# OBC_My_INTERFACE.net
KiCad netlist of a schematic drawn in Altium Designer
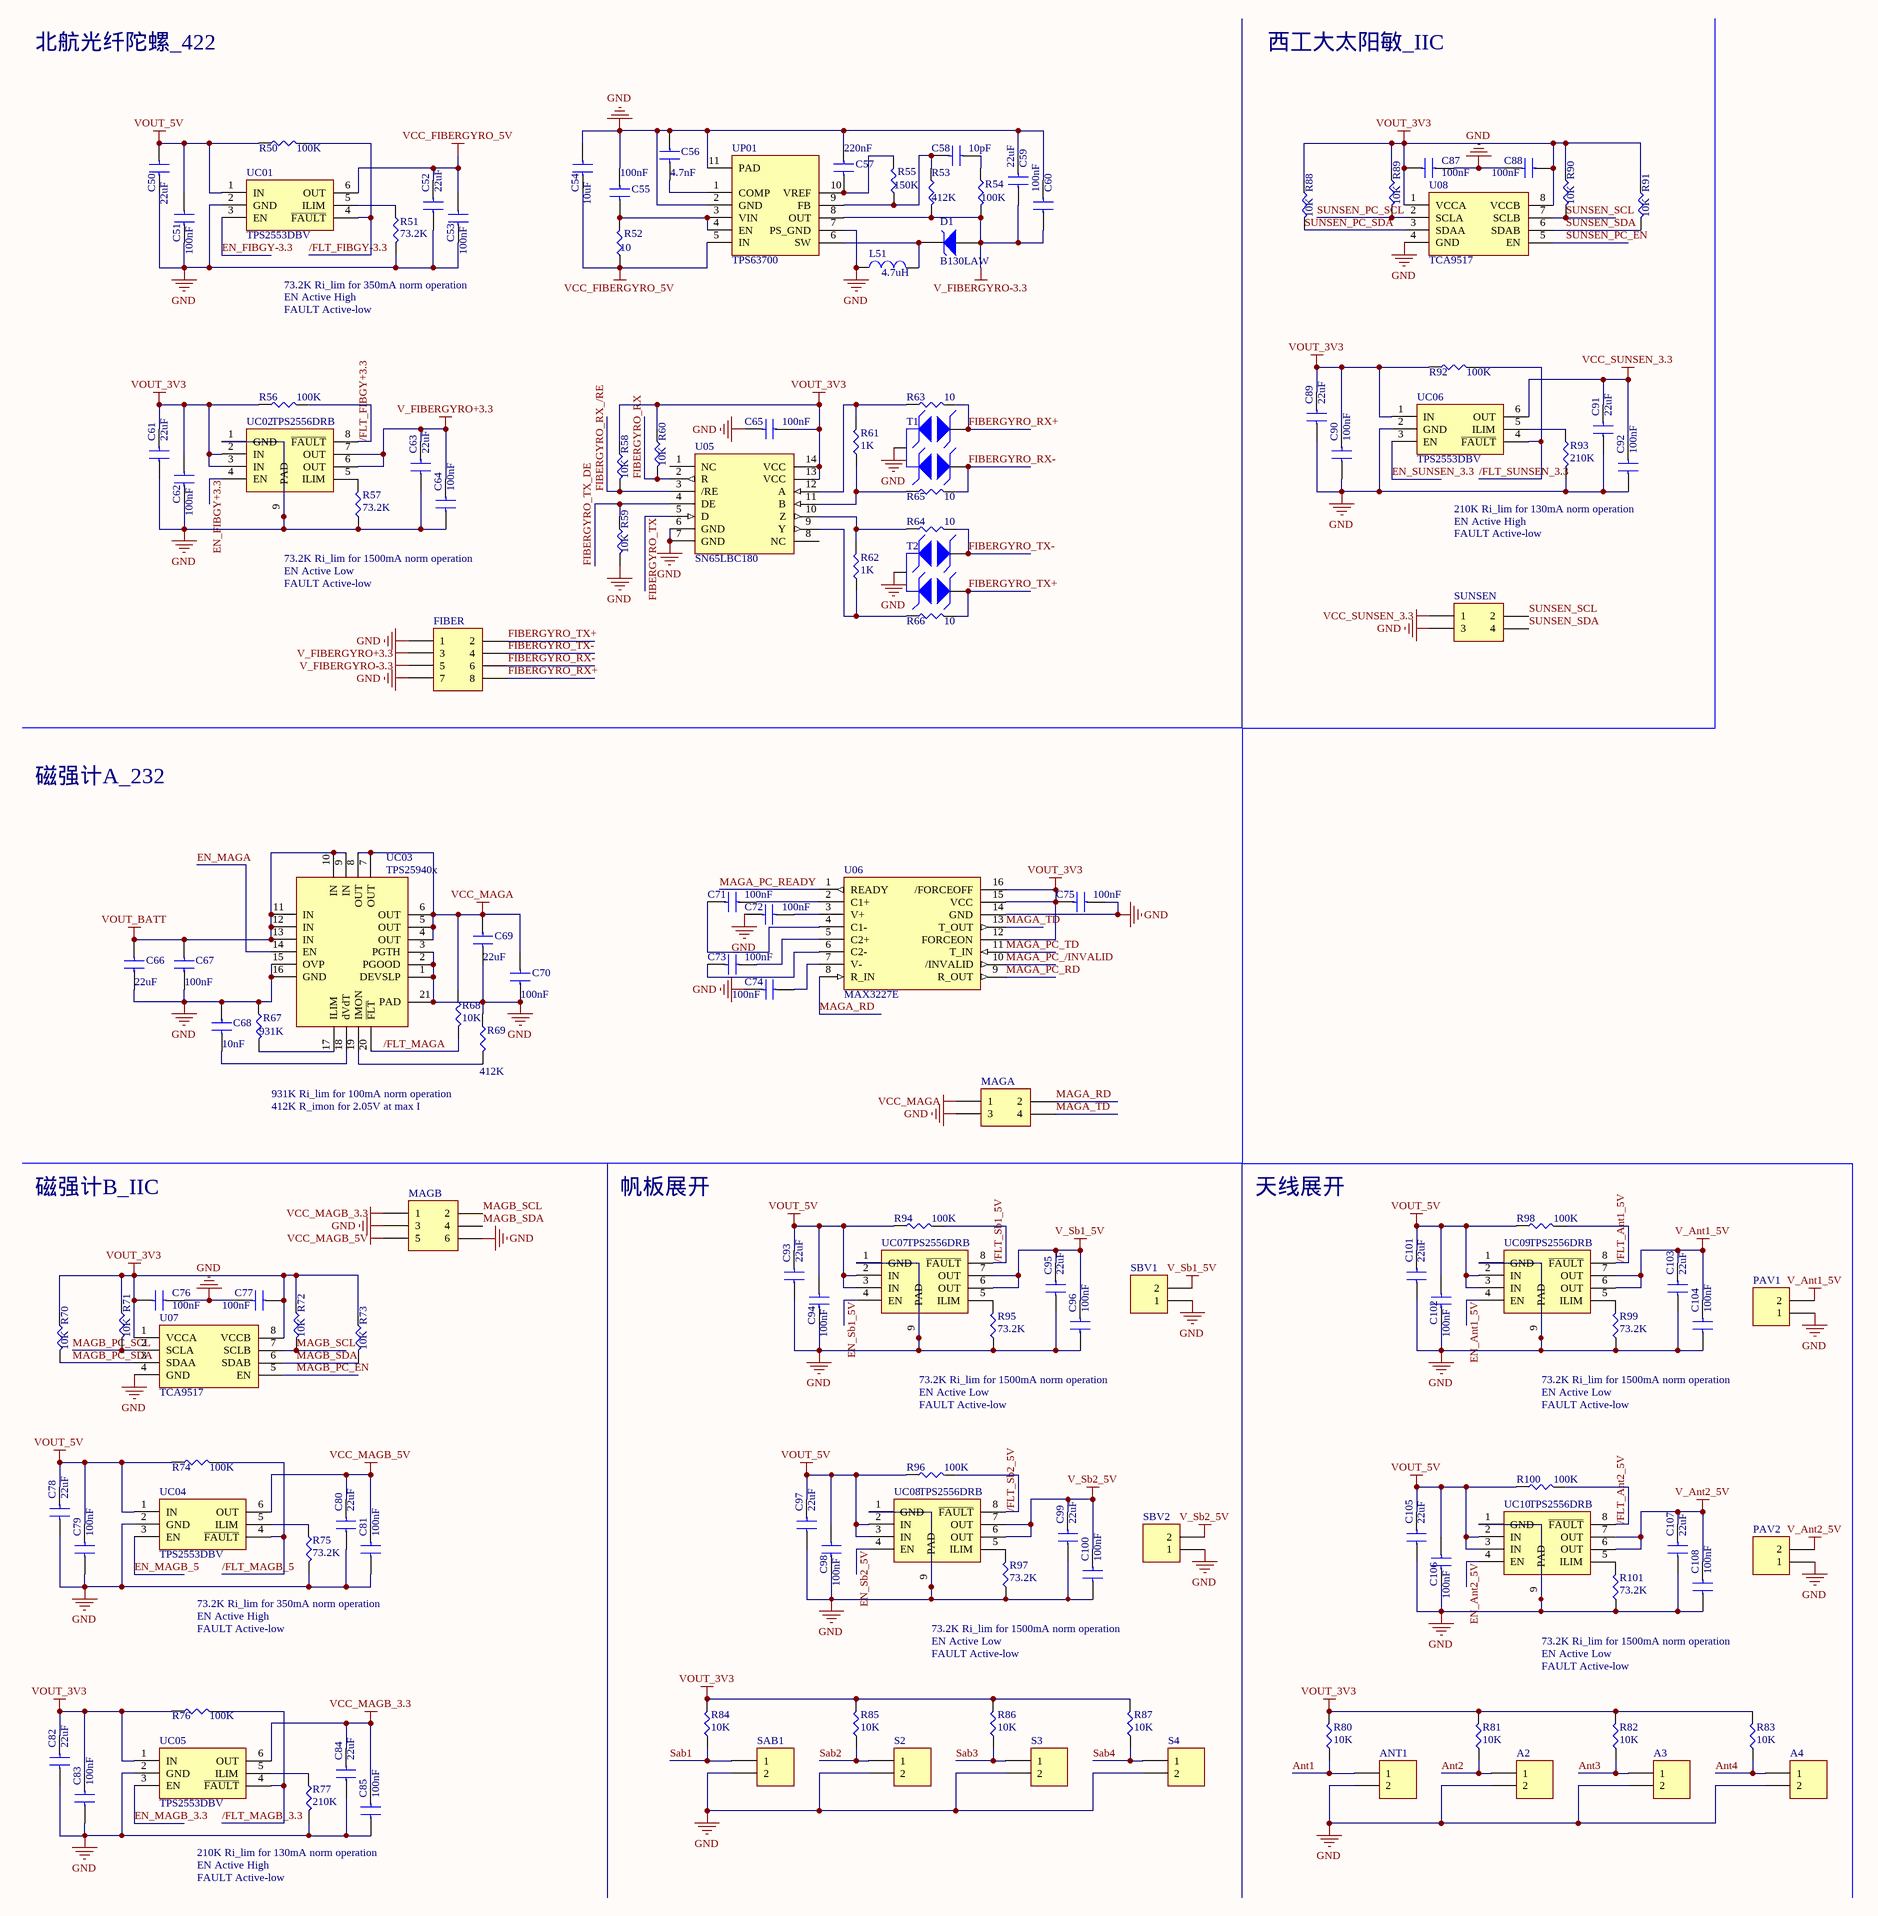
[diagram p0: OBC_My_INTERFACE.SchDoc]

(export (version "E")
  (design (tool "Eeschema 10.0.6"))
  (components
    (comp (ref "A2")
      (value "Header 2")
      (footprint "HDR1X2")
      (description "Header, 2-Pin")
      (fields (field (name "PUBLISHER") "Altium Limited"))
      (libsource (lib "Miscellaneous Connectors") (part "Header 2"))
    )
    (comp (ref "A3")
      (value "Header 2")
      (footprint "HDR1X2")
      (description "Header, 2-Pin")
      (fields (field (name "PUBLISHER") "Altium Limited"))
      (libsource (lib "Miscellaneous Connectors") (part "Header 2"))
    )
    (comp (ref "A4")
      (value "Header 2")
      (footprint "HDR1X2")
      (description "Header, 2-Pin")
      (fields (field (name "PUBLISHER") "Altium Limited"))
      (libsource (lib "Miscellaneous Connectors") (part "Header 2"))
    )
    (comp (ref "ANT1")
      (value "Header 2")
      (footprint "HDR1X2")
      (description "Header, 2-Pin")
      (fields (field (name "PUBLISHER") "Altium Limited"))
      (libsource (lib "Miscellaneous Connectors") (part "Header 2"))
    )
    (comp (ref "C50")
      (value "22uF")
      (footprint "1210(3225)-C-IPC")
      (description "Nonpolarized Capacitor (Surface Mount)")
      (libsource (lib "General Components") (part "Cap_1"))
    )
    (comp (ref "C51")
      (value "100nF")
      (footprint "0805(2012)-C-IPC")
      (description "Nonpolarized Capacitor (Surface Mount)")
      (libsource (lib "General Components") (part "Cap_1"))
    )
    (comp (ref "C52")
      (value "22uF")
      (footprint "1210(3225)-C-IPC")
      (description "Nonpolarized Capacitor (Surface Mount)")
      (libsource (lib "General Components") (part "Cap_1"))
    )
    (comp (ref "C53")
      (value "100nF")
      (footprint "0805(2012)-C-IPC")
      (description "Nonpolarized Capacitor (Surface Mount)")
      (libsource (lib "General Components") (part "Cap_1"))
    )
    (comp (ref "C54")
      (value "10uF")
      (footprint "0805(2012)-C-IPC")
      (description "Nonpolarized Capacitor (Surface Mount)")
      (libsource (lib "General Components") (part "Cap_1"))
    )
    (comp (ref "C55")
      (value "100nF")
      (footprint "0603(1608)-C-IPC")
      (description "Nonpolarized Capacitor (Surface Mount)")
      (libsource (lib "General Components") (part "Cap_1"))
    )
    (comp (ref "C56")
      (value "4.7nF")
      (footprint "0603(1608)-C-IPC")
      (description "Nonpolarized Capacitor (Surface Mount)")
      (libsource (lib "General Components") (part "Cap_1"))
    )
    (comp (ref "C57")
      (value "220nF")
      (footprint "0603(1608)-C-IPC")
      (description "Nonpolarized Capacitor (Surface Mount)")
      (libsource (lib "General Components") (part "Cap_1"))
    )
    (comp (ref "C58")
      (value "10pF")
      (footprint "0603(1608)-C-IPC")
      (description "Nonpolarized Capacitor (Surface Mount)")
      (libsource (lib "General Components") (part "Cap_1"))
    )
    (comp (ref "C59")
      (value "22uF")
      (footprint "1210(3225)-C-IPC")
      (description "Nonpolarized Capacitor (Surface Mount)")
      (libsource (lib "General Components") (part "Cap_1"))
    )
    (comp (ref "C60")
      (value "100nF")
      (footprint "0805(2012)-C-IPC")
      (description "Nonpolarized Capacitor (Surface Mount)")
      (libsource (lib "General Components") (part "Cap_1"))
    )
    (comp (ref "C61")
      (value "22uF")
      (footprint "1210(3225)-C-IPC")
      (description "Nonpolarized Capacitor (Surface Mount)")
      (libsource (lib "General Components") (part "Cap_1"))
    )
    (comp (ref "C62")
      (value "100nF")
      (footprint "0805(2012)-C-IPC")
      (description "Nonpolarized Capacitor (Surface Mount)")
      (libsource (lib "General Components") (part "Cap_1"))
    )
    (comp (ref "C63")
      (value "22uF")
      (footprint "1210(3225)-C-IPC")
      (description "Nonpolarized Capacitor (Surface Mount)")
      (libsource (lib "General Components") (part "Cap_1"))
    )
    (comp (ref "C64")
      (value "100nF")
      (footprint "0805(2012)-C-IPC")
      (description "Nonpolarized Capacitor (Surface Mount)")
      (libsource (lib "General Components") (part "Cap_1"))
    )
    (comp (ref "C65")
      (value "100nF")
      (footprint "0603(1608)-C-IPC")
      (description "Nonpolarized Capacitor (Surface Mount)")
      (libsource (lib "General Components") (part "Cap_1"))
    )
    (comp (ref "C66")
      (value "22uF")
      (footprint "1210(3225)-C-IPC")
      (description "Nonpolarized Capacitor (Surface Mount)")
      (libsource (lib "General Components") (part "Cap_1"))
    )
    (comp (ref "C67")
      (value "100nF")
      (footprint "0805(2012)-C-IPC")
      (description "Nonpolarized Capacitor (Surface Mount)")
      (libsource (lib "General Components") (part "Cap_1"))
    )
    (comp (ref "C68")
      (value "10nF")
      (footprint "0603(1608)-C-IPC")
      (description "Nonpolarized Capacitor (Surface Mount)")
      (libsource (lib "General Components") (part "Cap_1"))
    )
    (comp (ref "C69")
      (value "22uF")
      (footprint "1210(3225)-C-IPC")
      (description "Nonpolarized Capacitor (Surface Mount)")
      (libsource (lib "General Components") (part "Cap_1"))
    )
    (comp (ref "C70")
      (value "100nF")
      (footprint "0805(2012)-C-IPC")
      (description "Nonpolarized Capacitor (Surface Mount)")
      (libsource (lib "General Components") (part "Cap_1"))
    )
    (comp (ref "C71")
      (value "100nF")
      (footprint "0603(1608)-C-IPC")
      (description "Nonpolarized Capacitor (Surface Mount)")
      (libsource (lib "General Components") (part "Cap_1"))
    )
    (comp (ref "C72")
      (value "100nF")
      (footprint "0603(1608)-C-IPC")
      (description "Nonpolarized Capacitor (Surface Mount)")
      (libsource (lib "General Components") (part "Cap_1"))
    )
    (comp (ref "C73")
      (value "100nF")
      (footprint "0603(1608)-C-IPC")
      (description "Nonpolarized Capacitor (Surface Mount)")
      (libsource (lib "General Components") (part "Cap_1"))
    )
    (comp (ref "C74")
      (value "100nF")
      (footprint "0603(1608)-C-IPC")
      (description "Nonpolarized Capacitor (Surface Mount)")
      (libsource (lib "General Components") (part "Cap_1"))
    )
    (comp (ref "C75")
      (value "100nF")
      (footprint "0603(1608)-C-IPC")
      (description "Nonpolarized Capacitor (Surface Mount)")
      (libsource (lib "General Components") (part "Cap_1"))
    )
    (comp (ref "C76")
      (value "100nF")
      (footprint "0603(1608)-C-IPC")
      (description "Nonpolarized Capacitor (Surface Mount)")
      (libsource (lib "General Components") (part "Cap_1"))
    )
    (comp (ref "C77")
      (value "100nF")
      (footprint "0603(1608)-C-IPC")
      (description "Nonpolarized Capacitor (Surface Mount)")
      (libsource (lib "General Components") (part "Cap_1"))
    )
    (comp (ref "C78")
      (value "22uF")
      (footprint "1210(3225)-C-IPC")
      (description "Nonpolarized Capacitor (Surface Mount)")
      (libsource (lib "General Components") (part "Cap_1"))
    )
    (comp (ref "C79")
      (value "100nF")
      (footprint "0805(2012)-C-IPC")
      (description "Nonpolarized Capacitor (Surface Mount)")
      (libsource (lib "General Components") (part "Cap_1"))
    )
    (comp (ref "C80")
      (value "22uF")
      (footprint "1210(3225)-C-IPC")
      (description "Nonpolarized Capacitor (Surface Mount)")
      (libsource (lib "General Components") (part "Cap_1"))
    )
    (comp (ref "C81")
      (value "100nF")
      (footprint "0805(2012)-C-IPC")
      (description "Nonpolarized Capacitor (Surface Mount)")
      (libsource (lib "General Components") (part "Cap_1"))
    )
    (comp (ref "C82")
      (value "22uF")
      (footprint "1210(3225)-C-IPC")
      (description "Nonpolarized Capacitor (Surface Mount)")
      (libsource (lib "General Components") (part "Cap_1"))
    )
    (comp (ref "C83")
      (value "100nF")
      (footprint "0805(2012)-C-IPC")
      (description "Nonpolarized Capacitor (Surface Mount)")
      (libsource (lib "General Components") (part "Cap_1"))
    )
    (comp (ref "C84")
      (value "22uF")
      (footprint "1210(3225)-C-IPC")
      (description "Nonpolarized Capacitor (Surface Mount)")
      (libsource (lib "General Components") (part "Cap_1"))
    )
    (comp (ref "C85")
      (value "100nF")
      (footprint "0805(2012)-C-IPC")
      (description "Nonpolarized Capacitor (Surface Mount)")
      (libsource (lib "General Components") (part "Cap_1"))
    )
    (comp (ref "C87")
      (value "100nF")
      (footprint "0603(1608)-C-IPC")
      (description "Nonpolarized Capacitor (Surface Mount)")
      (libsource (lib "General Components") (part "Cap_1"))
    )
    (comp (ref "C88")
      (value "100nF")
      (footprint "0603(1608)-C-IPC")
      (description "Nonpolarized Capacitor (Surface Mount)")
      (libsource (lib "General Components") (part "Cap_1"))
    )
    (comp (ref "C89")
      (value "22uF")
      (footprint "1210(3225)-C-IPC")
      (description "Nonpolarized Capacitor (Surface Mount)")
      (libsource (lib "General Components") (part "Cap_1"))
    )
    (comp (ref "C90")
      (value "100nF")
      (footprint "0805(2012)-C-IPC")
      (description "Nonpolarized Capacitor (Surface Mount)")
      (libsource (lib "General Components") (part "Cap_1"))
    )
    (comp (ref "C91")
      (value "22uF")
      (footprint "1210(3225)-C-IPC")
      (description "Nonpolarized Capacitor (Surface Mount)")
      (libsource (lib "General Components") (part "Cap_1"))
    )
    (comp (ref "C92")
      (value "100nF")
      (footprint "0805(2012)-C-IPC")
      (description "Nonpolarized Capacitor (Surface Mount)")
      (libsource (lib "General Components") (part "Cap_1"))
    )
    (comp (ref "C93")
      (value "22uF")
      (footprint "1210(3225)-C-IPC")
      (description "Nonpolarized Capacitor (Surface Mount)")
      (libsource (lib "General Components") (part "Cap_1"))
    )
    (comp (ref "C94")
      (value "100nF")
      (footprint "0805(2012)-C-IPC")
      (description "Nonpolarized Capacitor (Surface Mount)")
      (libsource (lib "General Components") (part "Cap_1"))
    )
    (comp (ref "C95")
      (value "22uF")
      (footprint "1210(3225)-C-IPC")
      (description "Nonpolarized Capacitor (Surface Mount)")
      (libsource (lib "General Components") (part "Cap_1"))
    )
    (comp (ref "C96")
      (value "100nF")
      (footprint "0805(2012)-C-IPC")
      (description "Nonpolarized Capacitor (Surface Mount)")
      (libsource (lib "General Components") (part "Cap_1"))
    )
    (comp (ref "C97")
      (value "22uF")
      (footprint "1210(3225)-C-IPC")
      (description "Nonpolarized Capacitor (Surface Mount)")
      (libsource (lib "General Components") (part "Cap_1"))
    )
    (comp (ref "C98")
      (value "100nF")
      (footprint "0805(2012)-C-IPC")
      (description "Nonpolarized Capacitor (Surface Mount)")
      (libsource (lib "General Components") (part "Cap_1"))
    )
    (comp (ref "C99")
      (value "22uF")
      (footprint "1210(3225)-C-IPC")
      (description "Nonpolarized Capacitor (Surface Mount)")
      (libsource (lib "General Components") (part "Cap_1"))
    )
    (comp (ref "C100")
      (value "100nF")
      (footprint "0805(2012)-C-IPC")
      (description "Nonpolarized Capacitor (Surface Mount)")
      (libsource (lib "General Components") (part "Cap_1"))
    )
    (comp (ref "C101")
      (value "22uF")
      (footprint "1210(3225)-C-IPC")
      (description "Nonpolarized Capacitor (Surface Mount)")
      (libsource (lib "General Components") (part "Cap_1"))
    )
    (comp (ref "C102")
      (value "100nF")
      (footprint "0805(2012)-C-IPC")
      (description "Nonpolarized Capacitor (Surface Mount)")
      (libsource (lib "General Components") (part "Cap_1"))
    )
    (comp (ref "C103")
      (value "22uF")
      (footprint "1210(3225)-C-IPC")
      (description "Nonpolarized Capacitor (Surface Mount)")
      (libsource (lib "General Components") (part "Cap_1"))
    )
    (comp (ref "C104")
      (value "100nF")
      (footprint "0805(2012)-C-IPC")
      (description "Nonpolarized Capacitor (Surface Mount)")
      (libsource (lib "General Components") (part "Cap_1"))
    )
    (comp (ref "C105")
      (value "22uF")
      (footprint "1210(3225)-C-IPC")
      (description "Nonpolarized Capacitor (Surface Mount)")
      (libsource (lib "General Components") (part "Cap_1"))
    )
    (comp (ref "C106")
      (value "100nF")
      (footprint "0805(2012)-C-IPC")
      (description "Nonpolarized Capacitor (Surface Mount)")
      (libsource (lib "General Components") (part "Cap_1"))
    )
    (comp (ref "C107")
      (value "22uF")
      (footprint "1210(3225)-C-IPC")
      (description "Nonpolarized Capacitor (Surface Mount)")
      (libsource (lib "General Components") (part "Cap_1"))
    )
    (comp (ref "C108")
      (value "100nF")
      (footprint "0805(2012)-C-IPC")
      (description "Nonpolarized Capacitor (Surface Mount)")
      (libsource (lib "General Components") (part "Cap_1"))
    )
    (comp (ref "D1")
      (value "B130LAW")
      (footprint "SOD-123-D-IPC")
      (description "Schottky Diode")
      (libsource (lib "General Components") (part "D Schottky"))
    )
    (comp (ref "FIBER")
      (value "Header 4X2")
      (footprint "HDR2X4")
      (description "Header, 4-Pin, Dual row")
      (fields (field (name "PUBLISHER") "Altium Limited"))
      (libsource (lib "Miscellaneous Connectors") (part "Header 4X2"))
    )
    (comp (ref "L51")
      (value "4.7uH")
      (footprint "Inductor-CoilCraft-XAL40xx")
      (description "Inductor")
      (fields (field (name "Comment") "XAL4030-472"))
      (libsource (lib "General Components") (part "Inductor_1"))
    )
    (comp (ref "MAGA")
      (value "Header 2X2")
      (footprint "HDR2X2")
      (description "Header, 2-Pin, Dual row")
      (fields (field (name "PUBLISHER") "Altium Limited"))
      (libsource (lib "Miscellaneous Connectors") (part "Header 2X2"))
    )
    (comp (ref "MAGB")
      (value "Header 3X2")
      (footprint "HDR2X3")
      (description "Header, 3-Pin, Dual row")
      (fields (field (name "PUBLISHER") "Altium Limited"))
      (libsource (lib "Miscellaneous Connectors") (part "Header 3X2"))
    )
    (comp (ref "PAV1")
      (value "Header 2")
      (footprint "HDR1X2")
      (description "Header, 2-Pin")
      (fields (field (name "PUBLISHER") "Altium Limited"))
      (libsource (lib "") (part "Header 2_1"))
    )
    (comp (ref "PAV2")
      (value "Header 2")
      (footprint "HDR1X2")
      (description "Header, 2-Pin")
      (fields (field (name "PUBLISHER") "Altium Limited"))
      (libsource (lib "") (part "Header 2_1"))
    )
    (comp (ref "R50")
      (value "100K")
      (footprint "0603(1608)-R-IPC")
      (description "Resistor")
      (libsource (lib "General Components") (part "Res_1"))
    )
    (comp (ref "R51")
      (value "73.2K")
      (footprint "0603(1608)-R-IPC")
      (description "Resistor")
      (libsource (lib "General Components") (part "Res_1"))
    )
    (comp (ref "R52")
      (value "10")
      (footprint "0603(1608)-R-IPC")
      (description "Resistor")
      (libsource (lib "General Components") (part "Res_1"))
    )
    (comp (ref "R53")
      (value "412K")
      (footprint "0603(1608)-R-IPC")
      (description "Resistor")
      (libsource (lib "General Components") (part "Res_1"))
    )
    (comp (ref "R54")
      (value "100K")
      (footprint "0603(1608)-R-IPC")
      (description "Resistor")
      (libsource (lib "General Components") (part "Res_1"))
    )
    (comp (ref "R55")
      (value "150K")
      (footprint "0603(1608)-R-IPC")
      (description "Resistor")
      (libsource (lib "General Components") (part "Res_1"))
    )
    (comp (ref "R56")
      (value "100K")
      (footprint "0603(1608)-R-IPC")
      (description "Resistor")
      (libsource (lib "General Components") (part "Res_1"))
    )
    (comp (ref "R57")
      (value "73.2K")
      (footprint "0603(1608)-R-IPC")
      (description "Resistor")
      (libsource (lib "General Components") (part "Res_1"))
    )
    (comp (ref "R58")
      (value "10K")
      (footprint "0603(1608)-R-IPC")
      (description "Resistor")
      (libsource (lib "General Components") (part "Res_1"))
    )
    (comp (ref "R59")
      (value "10K")
      (footprint "0603(1608)-R-IPC")
      (description "Resistor")
      (libsource (lib "General Components") (part "Res_1"))
    )
    (comp (ref "R60")
      (value "10K")
      (footprint "0603(1608)-R-IPC")
      (description "Resistor")
      (libsource (lib "General Components") (part "Res_1"))
    )
    (comp (ref "R61")
      (value "1K")
      (footprint "0603(1608)-R-IPC")
      (description "Resistor")
      (fields (field (name "Comment") "Rt"))
      (libsource (lib "General Components") (part "Res_1"))
    )
    (comp (ref "R62")
      (value "1K")
      (footprint "0603(1608)-R-IPC")
      (description "Resistor")
      (fields (field (name "Comment") "Rt"))
      (libsource (lib "General Components") (part "Res_1"))
    )
    (comp (ref "R63")
      (value "10")
      (footprint "0603(1608)-R-IPC")
      (description "Resistor")
      (libsource (lib "General Components") (part "Res_1"))
    )
    (comp (ref "R64")
      (value "10")
      (footprint "0603(1608)-R-IPC")
      (description "Resistor")
      (libsource (lib "General Components") (part "Res_1"))
    )
    (comp (ref "R65")
      (value "10")
      (footprint "0603(1608)-R-IPC")
      (description "Resistor")
      (libsource (lib "General Components") (part "Res_1"))
    )
    (comp (ref "R66")
      (value "10")
      (footprint "0603(1608)-R-IPC")
      (description "Resistor")
      (libsource (lib "General Components") (part "Res_1"))
    )
    (comp (ref "R67")
      (value "931K")
      (footprint "0603(1608)-R-IPC")
      (description "Resistor")
      (libsource (lib "General Components") (part "Res_1"))
    )
    (comp (ref "R68")
      (value "10K")
      (footprint "0603(1608)-R-IPC")
      (description "Resistor")
      (libsource (lib "General Components") (part "Res_1"))
    )
    (comp (ref "R69")
      (value "412K")
      (footprint "0603(1608)-R-IPC")
      (description "Resistor")
      (libsource (lib "General Components") (part "Res_1"))
    )
    (comp (ref "R70")
      (value "10K")
      (footprint "0603(1608)-R-IPC")
      (description "Resistor")
      (libsource (lib "General Components") (part "Res_1"))
    )
    (comp (ref "R71")
      (value "10K")
      (footprint "0603(1608)-R-IPC")
      (description "Resistor")
      (libsource (lib "General Components") (part "Res_1"))
    )
    (comp (ref "R72")
      (value "10K")
      (footprint "0603(1608)-R-IPC")
      (description "Resistor")
      (libsource (lib "General Components") (part "Res_1"))
    )
    (comp (ref "R73")
      (value "10K")
      (footprint "0603(1608)-R-IPC")
      (description "Resistor")
      (libsource (lib "General Components") (part "Res_1"))
    )
    (comp (ref "R74")
      (value "100K")
      (footprint "0603(1608)-R-IPC")
      (description "Resistor")
      (libsource (lib "General Components") (part "Res_1"))
    )
    (comp (ref "R75")
      (value "73.2K")
      (footprint "0603(1608)-R-IPC")
      (description "Resistor")
      (libsource (lib "General Components") (part "Res_1"))
    )
    (comp (ref "R76")
      (value "100K")
      (footprint "0603(1608)-R-IPC")
      (description "Resistor")
      (libsource (lib "General Components") (part "Res_1"))
    )
    (comp (ref "R77")
      (value "210K")
      (footprint "0603(1608)-R-IPC")
      (description "Resistor")
      (libsource (lib "General Components") (part "Res_1"))
    )
    (comp (ref "R80")
      (value "10K")
      (footprint "0603(1608)-R-IPC")
      (description "Resistor")
      (libsource (lib "General Components") (part "Res_1"))
    )
    (comp (ref "R81")
      (value "10K")
      (footprint "0603(1608)-R-IPC")
      (description "Resistor")
      (libsource (lib "General Components") (part "Res_1"))
    )
    (comp (ref "R82")
      (value "10K")
      (footprint "0603(1608)-R-IPC")
      (description "Resistor")
      (libsource (lib "General Components") (part "Res_1"))
    )
    (comp (ref "R83")
      (value "10K")
      (footprint "0603(1608)-R-IPC")
      (description "Resistor")
      (libsource (lib "General Components") (part "Res_1"))
    )
    (comp (ref "R84")
      (value "10K")
      (footprint "0603(1608)-R-IPC")
      (description "Resistor")
      (libsource (lib "General Components") (part "Res_1"))
    )
    (comp (ref "R85")
      (value "10K")
      (footprint "0603(1608)-R-IPC")
      (description "Resistor")
      (libsource (lib "General Components") (part "Res_1"))
    )
    (comp (ref "R86")
      (value "10K")
      (footprint "0603(1608)-R-IPC")
      (description "Resistor")
      (libsource (lib "General Components") (part "Res_1"))
    )
    (comp (ref "R87")
      (value "10K")
      (footprint "0603(1608)-R-IPC")
      (description "Resistor")
      (libsource (lib "General Components") (part "Res_1"))
    )
    (comp (ref "R88")
      (value "10K")
      (footprint "0603(1608)-R-IPC")
      (description "Resistor")
      (libsource (lib "General Components") (part "Res_1"))
    )
    (comp (ref "R89")
      (value "10K")
      (footprint "0603(1608)-R-IPC")
      (description "Resistor")
      (libsource (lib "General Components") (part "Res_1"))
    )
    (comp (ref "R90")
      (value "10K")
      (footprint "0603(1608)-R-IPC")
      (description "Resistor")
      (libsource (lib "General Components") (part "Res_1"))
    )
    (comp (ref "R91")
      (value "10K")
      (footprint "0603(1608)-R-IPC")
      (description "Resistor")
      (libsource (lib "General Components") (part "Res_1"))
    )
    (comp (ref "R92")
      (value "100K")
      (footprint "0603(1608)-R-IPC")
      (description "Resistor")
      (libsource (lib "General Components") (part "Res_1"))
    )
    (comp (ref "R93")
      (value "210K")
      (footprint "0603(1608)-R-IPC")
      (description "Resistor")
      (libsource (lib "General Components") (part "Res_1"))
    )
    (comp (ref "R94")
      (value "100K")
      (footprint "0603(1608)-R-IPC")
      (description "Resistor")
      (libsource (lib "General Components") (part "Res_1"))
    )
    (comp (ref "R95")
      (value "73.2K")
      (footprint "0603(1608)-R-IPC")
      (description "Resistor")
      (libsource (lib "General Components") (part "Res_1"))
    )
    (comp (ref "R96")
      (value "100K")
      (footprint "0603(1608)-R-IPC")
      (description "Resistor")
      (libsource (lib "General Components") (part "Res_1"))
    )
    (comp (ref "R97")
      (value "73.2K")
      (footprint "0603(1608)-R-IPC")
      (description "Resistor")
      (libsource (lib "General Components") (part "Res_1"))
    )
    (comp (ref "R98")
      (value "100K")
      (footprint "0603(1608)-R-IPC")
      (description "Resistor")
      (libsource (lib "General Components") (part "Res_1"))
    )
    (comp (ref "R99")
      (value "73.2K")
      (footprint "0603(1608)-R-IPC")
      (description "Resistor")
      (libsource (lib "General Components") (part "Res_1"))
    )
    (comp (ref "R100")
      (value "100K")
      (footprint "0603(1608)-R-IPC")
      (description "Resistor")
      (libsource (lib "General Components") (part "Res_1"))
    )
    (comp (ref "R101")
      (value "73.2K")
      (footprint "0603(1608)-R-IPC")
      (description "Resistor")
      (libsource (lib "General Components") (part "Res_1"))
    )
    (comp (ref "S2")
      (value "Header 2")
      (footprint "HDR1X2")
      (description "Header, 2-Pin")
      (fields (field (name "PUBLISHER") "Altium Limited"))
      (libsource (lib "Miscellaneous Connectors") (part "Header 2"))
    )
    (comp (ref "S3")
      (value "Header 2")
      (footprint "HDR1X2")
      (description "Header, 2-Pin")
      (fields (field (name "PUBLISHER") "Altium Limited"))
      (libsource (lib "Miscellaneous Connectors") (part "Header 2"))
    )
    (comp (ref "S4")
      (value "Header 2")
      (footprint "HDR1X2")
      (description "Header, 2-Pin")
      (fields (field (name "PUBLISHER") "Altium Limited"))
      (libsource (lib "Miscellaneous Connectors") (part "Header 2"))
    )
    (comp (ref "SAB1")
      (value "Header 2")
      (footprint "HDR1X2")
      (description "Header, 2-Pin")
      (fields (field (name "PUBLISHER") "Altium Limited"))
      (libsource (lib "Miscellaneous Connectors") (part "Header 2"))
    )
    (comp (ref "SBV1")
      (value "Header 2")
      (footprint "HDR1X2")
      (description "Header, 2-Pin")
      (fields (field (name "PUBLISHER") "Altium Limited"))
      (libsource (lib "") (part "Header 2_1"))
    )
    (comp (ref "SBV2")
      (value "Header 2")
      (footprint "HDR1X2")
      (description "Header, 2-Pin")
      (fields (field (name "PUBLISHER") "Altium Limited"))
      (libsource (lib "") (part "Header 2_1"))
    )
    (comp (ref "SUNSEN")
      (value "Header 2X2")
      (footprint "HDR2X2")
      (description "Header, 2-Pin, Dual row")
      (fields (field (name "PUBLISHER") "Altium Limited"))
      (libsource (lib "Miscellaneous Connectors") (part "Header 2X2"))
    )
    (comp (ref "T1")
      (value "TVS-0502B")
      (footprint "SOT23-3")
      (description "ESD Protection Array")
      (libsource (lib "General Components") (part "TVS-0502B"))
    )
    (comp (ref "T2")
      (value "TVS-0502B")
      (footprint "SOT23-3")
      (description "ESD Protection Array")
      (libsource (lib "General Components") (part "TVS-0502B"))
    )
    (comp (ref "U05")
      (value "SN65LBC180")
      (footprint "SOIC127P600X175-14N")
      (description "3.3-V 422/485 Transceivers")
      (libsource (lib "TI Series") (part "SN65HVD76"))
    )
    (comp (ref "U06")
      (value "MAX3227E")
      (footprint "SSOP-16_208mil")
      (description "RS-232 Transceiver")
      (libsource (lib "TI Series") (part "MAX3227E"))
    )
    (comp (ref "U07")
      (value "TCA9517")
      (footprint "TSSOP-8-3x3-IPC")
      (description "I2C A-side drivers and B-side drivers")
      (libsource (lib "TI Series") (part "TCA9517"))
    )
    (comp (ref "U08")
      (value "TCA9517")
      (footprint "TSSOP-8-3x3-IPC")
      (description "I2C A-side drivers and B-side drivers")
      (libsource (lib "TI Series") (part "TCA9517"))
    )
    (comp (ref "UC01")
      (value "TPS2553DBV")
      (footprint "SOT23-6-IPC")
      (description "PRECISION ADJUSTABLE CURRENT-LIMITED POWER-DISTRIBUTION SWITCHES")
      (libsource (lib "TI Series") (part "TPS2553DBV"))
    )
    (comp (ref "UC02")
      (value "TPS2556DRB")
      (footprint "SON-8-3x3-w.TP-IPC")
      (description "PRECISION ADJUSTABLE CURRENT-LIMITED POWER-DISTRIBUTION SWITCHES")
      (libsource (lib "TI Series") (part "TPS2556DRB"))
    )
    (comp (ref "UC03")
      (value "TPS25940x")
      (footprint "QFN-20-0.5-3x4-w.TP-IPC")
      (description "18V eFuse with True Reverse Blocking and DevSleep Support for SSDs")
      (libsource (lib "TI Series") (part "TPS25940x"))
    )
    (comp (ref "UC04")
      (value "TPS2553DBV")
      (footprint "SOT23-6-IPC")
      (description "PRECISION ADJUSTABLE CURRENT-LIMITED POWER-DISTRIBUTION SWITCHES")
      (libsource (lib "TI Series") (part "TPS2553DBV"))
    )
    (comp (ref "UC05")
      (value "TPS2553DBV")
      (footprint "SOT23-6-IPC")
      (description "PRECISION ADJUSTABLE CURRENT-LIMITED POWER-DISTRIBUTION SWITCHES")
      (libsource (lib "TI Series") (part "TPS2553DBV"))
    )
    (comp (ref "UC06")
      (value "TPS2553DBV")
      (footprint "SOT23-6-IPC")
      (description "PRECISION ADJUSTABLE CURRENT-LIMITED POWER-DISTRIBUTION SWITCHES")
      (libsource (lib "TI Series") (part "TPS2553DBV"))
    )
    (comp (ref "UC07")
      (value "TPS2556DRB")
      (footprint "SON-8-3x3-w.TP-IPC")
      (description "PRECISION ADJUSTABLE CURRENT-LIMITED POWER-DISTRIBUTION SWITCHES")
      (libsource (lib "TI Series") (part "TPS2556DRB"))
    )
    (comp (ref "UC08")
      (value "TPS2556DRB")
      (footprint "SON-8-3x3-w.TP-IPC")
      (description "PRECISION ADJUSTABLE CURRENT-LIMITED POWER-DISTRIBUTION SWITCHES")
      (libsource (lib "TI Series") (part "TPS2556DRB"))
    )
    (comp (ref "UC09")
      (value "TPS2556DRB")
      (footprint "SON-8-3x3-w.TP-IPC")
      (description "PRECISION ADJUSTABLE CURRENT-LIMITED POWER-DISTRIBUTION SWITCHES")
      (libsource (lib "TI Series") (part "TPS2556DRB"))
    )
    (comp (ref "UC10")
      (value "TPS2556DRB")
      (footprint "SON-8-3x3-w.TP-IPC")
      (description "PRECISION ADJUSTABLE CURRENT-LIMITED POWER-DISTRIBUTION SWITCHES")
      (libsource (lib "TI Series") (part "TPS2556DRB"))
    )
    (comp (ref "UP01")
      (value "TPS63700")
      (footprint "DFN-10-0.5-3x3-w.TP-IPC")
      (description "DC-DC Inverter")
      (libsource (lib "TI Series") (part "TPS63700"))
    )
  )
  (nets
    (net (code "1") (name "/Ant1") (class "Default")
      (node (ref "ANT1") (pin "1") (pinfunction "1_1") (pintype "passive"))
      (node (ref "R80") (pin "1") (pinfunction "1_1") (pintype "passive"))
    )
    (net (code "2") (name "/Ant2") (class "Default")
      (node (ref "A2") (pin "1") (pinfunction "1_1") (pintype "passive"))
      (node (ref "R81") (pin "1") (pinfunction "1_1") (pintype "passive"))
    )
    (net (code "3") (name "/Ant3") (class "Default")
      (node (ref "A3") (pin "1") (pinfunction "1_1") (pintype "passive"))
      (node (ref "R82") (pin "1") (pinfunction "1_1") (pintype "passive"))
    )
    (net (code "4") (name "/Ant4") (class "Default")
      (node (ref "A4") (pin "1") (pinfunction "1_1") (pintype "passive"))
      (node (ref "R83") (pin "1") (pinfunction "1_1") (pintype "passive"))
    )
    (net (code "5") (name "/EN_Ant1_5V") (class "Default")
      (node (ref "UC09") (pin "4") (pinfunction "EN_4") (pintype "passive"))
    )
    (net (code "6") (name "/EN_Ant2_5V") (class "Default")
      (node (ref "UC10") (pin "4") (pinfunction "EN_4") (pintype "passive"))
    )
    (net (code "7") (name "/EN_FIBGY+3.3") (class "Default")
      (node (ref "UC02") (pin "4") (pinfunction "EN_4") (pintype "passive"))
    )
    (net (code "8") (name "/EN_FIBGY-3.3") (class "Default")
      (node (ref "UC01") (pin "3") (pinfunction "EN_3") (pintype "passive"))
    )
    (net (code "9") (name "/EN_MAGA") (class "Default")
      (node (ref "UC03") (pin "14") (pinfunction "EN_14") (pintype "passive"))
    )
    (net (code "10") (name "/EN_MAGB_3.3") (class "Default")
      (node (ref "UC05") (pin "3") (pinfunction "EN_3") (pintype "passive"))
    )
    (net (code "11") (name "/EN_MAGB_5") (class "Default")
      (node (ref "UC04") (pin "3") (pinfunction "EN_3") (pintype "passive"))
    )
    (net (code "12") (name "/EN_SUNSEN_3.3") (class "Default")
      (node (ref "UC06") (pin "3") (pinfunction "EN_3") (pintype "passive"))
    )
    (net (code "13") (name "/EN_Sb1_5V") (class "Default")
      (node (ref "UC07") (pin "4") (pinfunction "EN_4") (pintype "passive"))
    )
    (net (code "14") (name "/EN_Sb2_5V") (class "Default")
      (node (ref "UC08") (pin "4") (pinfunction "EN_4") (pintype "passive"))
    )
    (net (code "15") (name "/FIBERGYRO_RX") (class "Default")
      (node (ref "R60") (pin "2") (pinfunction "2_2") (pintype "passive"))
      (node (ref "U05") (pin "2") (pinfunction "R_2") (pintype "output"))
    )
    (net (code "16") (name "/FIBERGYRO_RX+") (class "Default")
      (node (ref "FIBER") (pin "8") (pinfunction "8_8") (pintype "passive"))
      (node (ref "R63") (pin "2") (pinfunction "2_2") (pintype "passive"))
      (node (ref "T1") (pin "2") (pinfunction "2_2") (pintype "power_in"))
    )
    (net (code "17") (name "/FIBERGYRO_RX-") (class "Default")
      (node (ref "FIBER") (pin "6") (pinfunction "6_6") (pintype "passive"))
      (node (ref "R65") (pin "2") (pinfunction "2_2") (pintype "passive"))
      (node (ref "T1") (pin "1") (pinfunction "1_1") (pintype "power_in"))
    )
    (net (code "18") (name "/FIBERGYRO_RX_{slash}RE") (class "Default")
      (node (ref "R58") (pin "2") (pinfunction "2_2") (pintype "passive"))
      (node (ref "U05") (pin "3") (pinfunction "/RE_3") (pintype "passive"))
    )
    (net (code "19") (name "/FIBERGYRO_TX") (class "Default")
      (node (ref "U05") (pin "5") (pinfunction "D_5") (pintype "input"))
    )
    (net (code "20") (name "/FIBERGYRO_TX+") (class "Default")
      (node (ref "FIBER") (pin "2") (pinfunction "2_2") (pintype "passive"))
      (node (ref "R66") (pin "2") (pinfunction "2_2") (pintype "passive"))
      (node (ref "T2") (pin "1") (pinfunction "1_1") (pintype "power_in"))
    )
    (net (code "21") (name "/FIBERGYRO_TX-") (class "Default")
      (node (ref "FIBER") (pin "4") (pinfunction "4_4") (pintype "passive"))
      (node (ref "R64") (pin "2") (pinfunction "2_2") (pintype "passive"))
      (node (ref "T2") (pin "2") (pinfunction "2_2") (pintype "power_in"))
    )
    (net (code "22") (name "/FIBERGYRO_TX_DE") (class "Default")
      (node (ref "R59") (pin "1") (pinfunction "1_1") (pintype "passive"))
      (node (ref "U05") (pin "4") (pinfunction "DE_4") (pintype "passive"))
    )
    (net (code "23") (name "/MAGA_PC_RD") (class "Default")
      (node (ref "U06") (pin "9") (pinfunction "R_OUT_9") (pintype "output"))
    )
    (net (code "24") (name "/MAGA_PC_READY") (class "Default")
      (node (ref "U06") (pin "1") (pinfunction "READY_1") (pintype "output"))
    )
    (net (code "25") (name "/MAGA_PC_TD") (class "Default")
      (node (ref "U06") (pin "11") (pinfunction "T_IN_11") (pintype "input"))
    )
    (net (code "26") (name "/MAGA_PC_{slash}INVALID") (class "Default")
      (node (ref "U06") (pin "10") (pinfunction "/INVALID_10") (pintype "output"))
    )
    (net (code "27") (name "/MAGA_RD") (class "Default")
      (node (ref "MAGA") (pin "2") (pinfunction "2_2") (pintype "passive"))
      (node (ref "U06") (pin "8") (pinfunction "R_IN_8") (pintype "input"))
    )
    (net (code "28") (name "/MAGA_TD") (class "Default")
      (node (ref "MAGA") (pin "4") (pinfunction "4_4") (pintype "passive"))
      (node (ref "U06") (pin "13") (pinfunction "T_OUT_13") (pintype "output"))
    )
    (net (code "29") (name "/MAGB_PC_EN") (class "Default")
      (node (ref "U07") (pin "5") (pinfunction "EN_5") (pintype "passive"))
    )
    (net (code "30") (name "/MAGB_PC_SCL") (class "Default")
      (node (ref "R71") (pin "2") (pinfunction "2_2") (pintype "passive"))
      (node (ref "U07") (pin "2") (pinfunction "SCLA_2") (pintype "passive"))
    )
    (net (code "31") (name "/MAGB_PC_SDA") (class "Default")
      (node (ref "R70") (pin "2") (pinfunction "2_2") (pintype "passive"))
      (node (ref "U07") (pin "3") (pinfunction "SDAA_3") (pintype "passive"))
    )
    (net (code "32") (name "/MAGB_SCL") (class "Default")
      (node (ref "MAGB") (pin "2") (pinfunction "2_2") (pintype "passive"))
      (node (ref "R72") (pin "2") (pinfunction "2_2") (pintype "passive"))
      (node (ref "U07") (pin "7") (pinfunction "SCLB_7") (pintype "passive"))
    )
    (net (code "33") (name "/MAGB_SDA") (class "Default")
      (node (ref "MAGB") (pin "4") (pinfunction "4_4") (pintype "passive"))
      (node (ref "R73") (pin "2") (pinfunction "2_2") (pintype "passive"))
      (node (ref "U07") (pin "6") (pinfunction "SDAB_6") (pintype "passive"))
    )
    (net (code "34") (name "/SUNSEN_PC_EN") (class "Default")
      (node (ref "U08") (pin "5") (pinfunction "EN_5") (pintype "passive"))
    )
    (net (code "35") (name "/SUNSEN_PC_SCL") (class "Default")
      (node (ref "R89") (pin "2") (pinfunction "2_2") (pintype "passive"))
      (node (ref "U08") (pin "2") (pinfunction "SCLA_2") (pintype "passive"))
    )
    (net (code "36") (name "/SUNSEN_PC_SDA") (class "Default")
      (node (ref "R88") (pin "2") (pinfunction "2_2") (pintype "passive"))
      (node (ref "U08") (pin "3") (pinfunction "SDAA_3") (pintype "passive"))
    )
    (net (code "37") (name "/SUNSEN_SCL") (class "Default")
      (node (ref "R90") (pin "2") (pinfunction "2_2") (pintype "passive"))
      (node (ref "SUNSEN") (pin "2") (pinfunction "2_2") (pintype "passive"))
      (node (ref "U08") (pin "7") (pinfunction "SCLB_7") (pintype "passive"))
    )
    (net (code "38") (name "/SUNSEN_SDA") (class "Default")
      (node (ref "R91") (pin "2") (pinfunction "2_2") (pintype "passive"))
      (node (ref "SUNSEN") (pin "4") (pinfunction "4_4") (pintype "passive"))
      (node (ref "U08") (pin "6") (pinfunction "SDAB_6") (pintype "passive"))
    )
    (net (code "39") (name "/Sab1") (class "Default")
      (node (ref "R84") (pin "1") (pinfunction "1_1") (pintype "passive"))
      (node (ref "SAB1") (pin "1") (pinfunction "1_1") (pintype "passive"))
    )
    (net (code "40") (name "/Sab2") (class "Default")
      (node (ref "R85") (pin "1") (pinfunction "1_1") (pintype "passive"))
      (node (ref "S2") (pin "1") (pinfunction "1_1") (pintype "passive"))
    )
    (net (code "41") (name "/Sab3") (class "Default")
      (node (ref "R86") (pin "1") (pinfunction "1_1") (pintype "passive"))
      (node (ref "S3") (pin "1") (pinfunction "1_1") (pintype "passive"))
    )
    (net (code "42") (name "/Sab4") (class "Default")
      (node (ref "R87") (pin "1") (pinfunction "1_1") (pintype "passive"))
      (node (ref "S4") (pin "1") (pinfunction "1_1") (pintype "passive"))
    )
    (net (code "43") (name "/{slash}FLT_Ant1_5V") (class "Default")
      (node (ref "R98") (pin "2") (pinfunction "2_2") (pintype "passive"))
      (node (ref "UC09") (pin "8") (pinfunction "~{FAULT}_8") (pintype "passive"))
    )
    (net (code "44") (name "/{slash}FLT_Ant2_5V") (class "Default")
      (node (ref "R100") (pin "2") (pinfunction "2_2") (pintype "passive"))
      (node (ref "UC10") (pin "8") (pinfunction "~{FAULT}_8") (pintype "passive"))
    )
    (net (code "45") (name "/{slash}FLT_FIBGY+3.3") (class "Default")
      (node (ref "R56") (pin "2") (pinfunction "2_2") (pintype "passive"))
      (node (ref "UC02") (pin "8") (pinfunction "~{FAULT}_8") (pintype "passive"))
    )
    (net (code "46") (name "/{slash}FLT_FIBGY-3.3") (class "Default")
      (node (ref "R50") (pin "2") (pinfunction "2_2") (pintype "passive"))
      (node (ref "UC01") (pin "4") (pinfunction "~{FAULT}_4") (pintype "passive"))
    )
    (net (code "47") (name "/{slash}FLT_MAGA") (class "Default")
      (node (ref "R68") (pin "2") (pinfunction "2_2") (pintype "passive"))
      (node (ref "UC03") (pin "20") (pinfunction "~{FLT}_20") (pintype "passive"))
    )
    (net (code "48") (name "/{slash}FLT_MAGB_3.3") (class "Default")
      (node (ref "R76") (pin "2") (pinfunction "2_2") (pintype "passive"))
      (node (ref "UC05") (pin "4") (pinfunction "~{FAULT}_4") (pintype "passive"))
    )
    (net (code "49") (name "/{slash}FLT_MAGB_5") (class "Default")
      (node (ref "R74") (pin "2") (pinfunction "2_2") (pintype "passive"))
      (node (ref "UC04") (pin "4") (pinfunction "~{FAULT}_4") (pintype "passive"))
    )
    (net (code "50") (name "/{slash}FLT_SUNSEN_3.3") (class "Default")
      (node (ref "R92") (pin "2") (pinfunction "2_2") (pintype "passive"))
      (node (ref "UC06") (pin "4") (pinfunction "~{FAULT}_4") (pintype "passive"))
    )
    (net (code "51") (name "/{slash}FLT_Sb1_5V") (class "Default")
      (node (ref "R94") (pin "2") (pinfunction "2_2") (pintype "passive"))
      (node (ref "UC07") (pin "8") (pinfunction "~{FAULT}_8") (pintype "passive"))
    )
    (net (code "52") (name "/{slash}FLT_Sb2_5V") (class "Default")
      (node (ref "R96") (pin "2") (pinfunction "2_2") (pintype "passive"))
      (node (ref "UC08") (pin "8") (pinfunction "~{FAULT}_8") (pintype "passive"))
    )
    (net (code "53") (name "GND") (class "Default")
      (node (ref "A2") (pin "2") (pinfunction "2_2") (pintype "passive"))
      (node (ref "A3") (pin "2") (pinfunction "2_2") (pintype "passive"))
      (node (ref "A4") (pin "2") (pinfunction "2_2") (pintype "passive"))
      (node (ref "ANT1") (pin "2") (pinfunction "2_2") (pintype "passive"))
      (node (ref "C100") (pin "2") (pinfunction "2_2") (pintype "passive"))
      (node (ref "C101") (pin "2") (pinfunction "2_2") (pintype "passive"))
      (node (ref "C102") (pin "2") (pinfunction "2_2") (pintype "passive"))
      (node (ref "C103") (pin "2") (pinfunction "2_2") (pintype "passive"))
      (node (ref "C104") (pin "2") (pinfunction "2_2") (pintype "passive"))
      (node (ref "C105") (pin "2") (pinfunction "2_2") (pintype "passive"))
      (node (ref "C106") (pin "2") (pinfunction "2_2") (pintype "passive"))
      (node (ref "C107") (pin "2") (pinfunction "2_2") (pintype "passive"))
      (node (ref "C108") (pin "2") (pinfunction "2_2") (pintype "passive"))
      (node (ref "C50") (pin "2") (pinfunction "2_2") (pintype "passive"))
      (node (ref "C51") (pin "2") (pinfunction "2_2") (pintype "passive"))
      (node (ref "C52") (pin "2") (pinfunction "2_2") (pintype "passive"))
      (node (ref "C53") (pin "2") (pinfunction "2_2") (pintype "passive"))
      (node (ref "C54") (pin "1") (pinfunction "1_1") (pintype "passive"))
      (node (ref "C55") (pin "2") (pinfunction "2_2") (pintype "passive"))
      (node (ref "C56") (pin "2") (pinfunction "2_2") (pintype "passive"))
      (node (ref "C57") (pin "2") (pinfunction "2_2") (pintype "passive"))
      (node (ref "C59") (pin "1") (pinfunction "1_1") (pintype "passive"))
      (node (ref "C60") (pin "1") (pinfunction "1_1") (pintype "passive"))
      (node (ref "C61") (pin "2") (pinfunction "2_2") (pintype "passive"))
      (node (ref "C62") (pin "2") (pinfunction "2_2") (pintype "passive"))
      (node (ref "C63") (pin "2") (pinfunction "2_2") (pintype "passive"))
      (node (ref "C64") (pin "2") (pinfunction "2_2") (pintype "passive"))
      (node (ref "C65") (pin "2") (pinfunction "2_2") (pintype "passive"))
      (node (ref "C66") (pin "2") (pinfunction "2_2") (pintype "passive"))
      (node (ref "C67") (pin "2") (pinfunction "2_2") (pintype "passive"))
      (node (ref "C68") (pin "2") (pinfunction "2_2") (pintype "passive"))
      (node (ref "C69") (pin "2") (pinfunction "2_2") (pintype "passive"))
      (node (ref "C70") (pin "2") (pinfunction "2_2") (pintype "passive"))
      (node (ref "C72") (pin "1") (pinfunction "1_1") (pintype "passive"))
      (node (ref "C74") (pin "2") (pinfunction "2_2") (pintype "passive"))
      (node (ref "C75") (pin "1") (pinfunction "1_1") (pintype "passive"))
      (node (ref "C76") (pin "2") (pinfunction "2_2") (pintype "passive"))
      (node (ref "C77") (pin "2") (pinfunction "2_2") (pintype "passive"))
      (node (ref "C78") (pin "2") (pinfunction "2_2") (pintype "passive"))
      (node (ref "C79") (pin "2") (pinfunction "2_2") (pintype "passive"))
      (node (ref "C80") (pin "2") (pinfunction "2_2") (pintype "passive"))
      (node (ref "C81") (pin "2") (pinfunction "2_2") (pintype "passive"))
      (node (ref "C82") (pin "2") (pinfunction "2_2") (pintype "passive"))
      (node (ref "C83") (pin "2") (pinfunction "2_2") (pintype "passive"))
      (node (ref "C84") (pin "2") (pinfunction "2_2") (pintype "passive"))
      (node (ref "C85") (pin "2") (pinfunction "2_2") (pintype "passive"))
      (node (ref "C87") (pin "2") (pinfunction "2_2") (pintype "passive"))
      (node (ref "C88") (pin "2") (pinfunction "2_2") (pintype "passive"))
      (node (ref "C89") (pin "2") (pinfunction "2_2") (pintype "passive"))
      (node (ref "C90") (pin "2") (pinfunction "2_2") (pintype "passive"))
      (node (ref "C91") (pin "2") (pinfunction "2_2") (pintype "passive"))
      (node (ref "C92") (pin "2") (pinfunction "2_2") (pintype "passive"))
      (node (ref "C93") (pin "2") (pinfunction "2_2") (pintype "passive"))
      (node (ref "C94") (pin "2") (pinfunction "2_2") (pintype "passive"))
      (node (ref "C95") (pin "2") (pinfunction "2_2") (pintype "passive"))
      (node (ref "C96") (pin "2") (pinfunction "2_2") (pintype "passive"))
      (node (ref "C97") (pin "2") (pinfunction "2_2") (pintype "passive"))
      (node (ref "C98") (pin "2") (pinfunction "2_2") (pintype "passive"))
      (node (ref "C99") (pin "2") (pinfunction "2_2") (pintype "passive"))
      (node (ref "FIBER") (pin "1") (pinfunction "1_1") (pintype "passive"))
      (node (ref "FIBER") (pin "7") (pinfunction "7_7") (pintype "passive"))
      (node (ref "L51") (pin "1") (pinfunction "1_1") (pintype "passive"))
      (node (ref "MAGA") (pin "3") (pinfunction "3_3") (pintype "passive"))
      (node (ref "MAGB") (pin "3") (pinfunction "3_3") (pintype "passive"))
      (node (ref "MAGB") (pin "6") (pinfunction "6_6") (pintype "passive"))
      (node (ref "PAV1") (pin "1") (pinfunction "1_1") (pintype "passive"))
      (node (ref "PAV2") (pin "1") (pinfunction "1_1") (pintype "passive"))
      (node (ref "R101") (pin "1") (pinfunction "1_1") (pintype "passive"))
      (node (ref "R51") (pin "2") (pinfunction "2_2") (pintype "passive"))
      (node (ref "R57") (pin "1") (pinfunction "1_1") (pintype "passive"))
      (node (ref "R59") (pin "2") (pinfunction "2_2") (pintype "passive"))
      (node (ref "R67") (pin "1") (pinfunction "1_1") (pintype "passive"))
      (node (ref "R69") (pin "1") (pinfunction "1_1") (pintype "passive"))
      (node (ref "R75") (pin "2") (pinfunction "2_2") (pintype "passive"))
      (node (ref "R77") (pin "2") (pinfunction "2_2") (pintype "passive"))
      (node (ref "R93") (pin "2") (pinfunction "2_2") (pintype "passive"))
      (node (ref "R95") (pin "1") (pinfunction "1_1") (pintype "passive"))
      (node (ref "R97") (pin "1") (pinfunction "1_1") (pintype "passive"))
      (node (ref "R99") (pin "1") (pinfunction "1_1") (pintype "passive"))
      (node (ref "S2") (pin "2") (pinfunction "2_2") (pintype "passive"))
      (node (ref "S3") (pin "2") (pinfunction "2_2") (pintype "passive"))
      (node (ref "S4") (pin "2") (pinfunction "2_2") (pintype "passive"))
      (node (ref "SAB1") (pin "2") (pinfunction "2_2") (pintype "passive"))
      (node (ref "SBV1") (pin "1") (pinfunction "1_1") (pintype "passive"))
      (node (ref "SBV2") (pin "1") (pinfunction "1_1") (pintype "passive"))
      (node (ref "SUNSEN") (pin "3") (pinfunction "3_3") (pintype "passive"))
      (node (ref "T1") (pin "3") (pinfunction "3_3") (pintype "power_in"))
      (node (ref "T2") (pin "3") (pinfunction "3_3") (pintype "power_in"))
      (node (ref "U05") (pin "6") (pinfunction "GND_6") (pintype "power_in"))
      (node (ref "U05") (pin "7") (pinfunction "GND_7") (pintype "power_in"))
      (node (ref "U06") (pin "14") (pinfunction "GND_14") (pintype "power_in"))
      (node (ref "U07") (pin "4") (pinfunction "GND_4") (pintype "passive"))
      (node (ref "U08") (pin "4") (pinfunction "GND_4") (pintype "passive"))
      (node (ref "UC01") (pin "2") (pinfunction "GND_2") (pintype "passive"))
      (node (ref "UC02") (pin "1") (pinfunction "GND_1") (pintype "passive"))
      (node (ref "UC02") (pin "9") (pinfunction "PAD_9") (pintype "passive"))
      (node (ref "UC03") (pin "1") (pinfunction "DEVSLP_1") (pintype "passive"))
      (node (ref "UC03") (pin "15") (pinfunction "OVP_15") (pintype "passive"))
      (node (ref "UC03") (pin "16") (pinfunction "GND_16") (pintype "passive"))
      (node (ref "UC03") (pin "2") (pinfunction "PGOOD_2") (pintype "passive"))
      (node (ref "UC03") (pin "21") (pinfunction "PAD_21") (pintype "passive"))
      (node (ref "UC03") (pin "3") (pinfunction "PGTH_3") (pintype "passive"))
      (node (ref "UC04") (pin "2") (pinfunction "GND_2") (pintype "passive"))
      (node (ref "UC05") (pin "2") (pinfunction "GND_2") (pintype "passive"))
      (node (ref "UC06") (pin "2") (pinfunction "GND_2") (pintype "passive"))
      (node (ref "UC07") (pin "1") (pinfunction "GND_1") (pintype "passive"))
      (node (ref "UC07") (pin "9") (pinfunction "PAD_9") (pintype "passive"))
      (node (ref "UC08") (pin "1") (pinfunction "GND_1") (pintype "passive"))
      (node (ref "UC08") (pin "9") (pinfunction "PAD_9") (pintype "passive"))
      (node (ref "UC09") (pin "1") (pinfunction "GND_1") (pintype "passive"))
      (node (ref "UC09") (pin "9") (pinfunction "PAD_9") (pintype "passive"))
      (node (ref "UC10") (pin "1") (pinfunction "GND_1") (pintype "passive"))
      (node (ref "UC10") (pin "9") (pinfunction "PAD_9") (pintype "passive"))
      (node (ref "UP01") (pin "11") (pinfunction "PAD_11") (pintype "passive"))
      (node (ref "UP01") (pin "2") (pinfunction "GND_2") (pintype "passive"))
      (node (ref "UP01") (pin "7") (pinfunction "PS_GND_7") (pintype "passive"))
    )
    (net (code "54") (name "Net-(C58-Pad1)") (class "Default")
      (node (ref "C58") (pin "1") (pinfunction "1_1") (pintype "passive"))
      (node (ref "R54") (pin "1") (pinfunction "1_1") (pintype "passive"))
    )
    (net (code "55") (name "Net-(D1-K)") (class "Default")
      (node (ref "D1") (pin "2") (pinfunction "K_2") (pintype "passive"))
      (node (ref "L51") (pin "2") (pinfunction "2_2") (pintype "passive"))
      (node (ref "UP01") (pin "6") (pinfunction "SW_6") (pintype "passive"))
    )
    (net (code "56") (name "Net-(U05-A)") (class "Default")
      (node (ref "R61") (pin "2") (pinfunction "2_2") (pintype "passive"))
      (node (ref "R63") (pin "1") (pinfunction "1_1") (pintype "passive"))
      (node (ref "U05") (pin "12") (pinfunction "A_12") (pintype "input"))
    )
    (net (code "57") (name "Net-(U05-B)") (class "Default")
      (node (ref "R61") (pin "1") (pinfunction "1_1") (pintype "passive"))
      (node (ref "R65") (pin "1") (pinfunction "1_1") (pintype "passive"))
      (node (ref "U05") (pin "11") (pinfunction "B_11") (pintype "input"))
    )
    (net (code "58") (name "Net-(U05-Y)") (class "Default")
      (node (ref "R62") (pin "1") (pinfunction "1_1") (pintype "passive"))
      (node (ref "R66") (pin "1") (pinfunction "1_1") (pintype "passive"))
      (node (ref "U05") (pin "9") (pinfunction "Y_9") (pintype "output"))
    )
    (net (code "59") (name "Net-(U05-Z)") (class "Default")
      (node (ref "R62") (pin "2") (pinfunction "2_2") (pintype "passive"))
      (node (ref "R64") (pin "1") (pinfunction "1_1") (pintype "passive"))
      (node (ref "U05") (pin "10") (pinfunction "Z_10") (pintype "output"))
    )
    (net (code "60") (name "Net-(U06-C1+)") (class "Default")
      (node (ref "C71") (pin "1") (pinfunction "1_1") (pintype "passive"))
      (node (ref "U06") (pin "2") (pinfunction "C1+_2") (pintype "passive"))
    )
    (net (code "61") (name "Net-(U06-C1-)") (class "Default")
      (node (ref "C71") (pin "2") (pinfunction "2_2") (pintype "passive"))
      (node (ref "U06") (pin "4") (pinfunction "C1-_4") (pintype "passive"))
    )
    (net (code "62") (name "Net-(U06-C2+)") (class "Default")
      (node (ref "C73") (pin "1") (pinfunction "1_1") (pintype "passive"))
      (node (ref "U06") (pin "5") (pinfunction "C2+_5") (pintype "passive"))
    )
    (net (code "63") (name "Net-(U06-C2-)") (class "Default")
      (node (ref "C73") (pin "2") (pinfunction "2_2") (pintype "passive"))
      (node (ref "U06") (pin "6") (pinfunction "C2-_6") (pintype "passive"))
    )
    (net (code "64") (name "Net-(U06-V+)") (class "Default")
      (node (ref "C72") (pin "2") (pinfunction "2_2") (pintype "passive"))
      (node (ref "U06") (pin "3") (pinfunction "V+_3") (pintype "passive"))
    )
    (net (code "65") (name "Net-(U06-V-)") (class "Default")
      (node (ref "C74") (pin "1") (pinfunction "1_1") (pintype "passive"))
      (node (ref "U06") (pin "7") (pinfunction "V-_7") (pintype "passive"))
    )
    (net (code "66") (name "Net-(UC01-ILIM)") (class "Default")
      (node (ref "R51") (pin "1") (pinfunction "1_1") (pintype "passive"))
      (node (ref "UC01") (pin "5") (pinfunction "ILIM_5") (pintype "passive"))
    )
    (net (code "67") (name "Net-(UC02-ILIM)") (class "Default")
      (node (ref "R57") (pin "2") (pinfunction "2_2") (pintype "passive"))
      (node (ref "UC02") (pin "5") (pinfunction "ILIM_5") (pintype "passive"))
    )
    (net (code "68") (name "Net-(UC03-ILIM)") (class "Default")
      (node (ref "R67") (pin "2") (pinfunction "2_2") (pintype "passive"))
      (node (ref "UC03") (pin "17") (pinfunction "ILIM_17") (pintype "passive"))
    )
    (net (code "69") (name "Net-(UC03-IMON)") (class "Default")
      (node (ref "R69") (pin "2") (pinfunction "2_2") (pintype "passive"))
      (node (ref "UC03") (pin "19") (pinfunction "IMON_19") (pintype "passive"))
    )
    (net (code "70") (name "Net-(UC03-dVdT)") (class "Default")
      (node (ref "C68") (pin "1") (pinfunction "1_1") (pintype "passive"))
      (node (ref "UC03") (pin "18") (pinfunction "dVdT_18") (pintype "passive"))
    )
    (net (code "71") (name "Net-(UC04-ILIM)") (class "Default")
      (node (ref "R75") (pin "1") (pinfunction "1_1") (pintype "passive"))
      (node (ref "UC04") (pin "5") (pinfunction "ILIM_5") (pintype "passive"))
    )
    (net (code "72") (name "Net-(UC05-ILIM)") (class "Default")
      (node (ref "R77") (pin "1") (pinfunction "1_1") (pintype "passive"))
      (node (ref "UC05") (pin "5") (pinfunction "ILIM_5") (pintype "passive"))
    )
    (net (code "73") (name "Net-(UC06-ILIM)") (class "Default")
      (node (ref "R93") (pin "1") (pinfunction "1_1") (pintype "passive"))
      (node (ref "UC06") (pin "5") (pinfunction "ILIM_5") (pintype "passive"))
    )
    (net (code "74") (name "Net-(UC07-ILIM)") (class "Default")
      (node (ref "R95") (pin "2") (pinfunction "2_2") (pintype "passive"))
      (node (ref "UC07") (pin "5") (pinfunction "ILIM_5") (pintype "passive"))
    )
    (net (code "75") (name "Net-(UC08-ILIM)") (class "Default")
      (node (ref "R97") (pin "2") (pinfunction "2_2") (pintype "passive"))
      (node (ref "UC08") (pin "5") (pinfunction "ILIM_5") (pintype "passive"))
    )
    (net (code "76") (name "Net-(UC09-ILIM)") (class "Default")
      (node (ref "R99") (pin "2") (pinfunction "2_2") (pintype "passive"))
      (node (ref "UC09") (pin "5") (pinfunction "ILIM_5") (pintype "passive"))
    )
    (net (code "77") (name "Net-(UC10-ILIM)") (class "Default")
      (node (ref "R101") (pin "2") (pinfunction "2_2") (pintype "passive"))
      (node (ref "UC10") (pin "5") (pinfunction "ILIM_5") (pintype "passive"))
    )
    (net (code "78") (name "Net-(UP01-COMP)") (class "Default")
      (node (ref "C56") (pin "1") (pinfunction "1_1") (pintype "passive"))
      (node (ref "UP01") (pin "1") (pinfunction "COMP_1") (pintype "passive"))
    )
    (net (code "79") (name "Net-(UP01-EN)") (class "Default")
      (node (ref "C55") (pin "1") (pinfunction "1_1") (pintype "passive"))
      (node (ref "R52") (pin "2") (pinfunction "2_2") (pintype "passive"))
      (node (ref "UP01") (pin "3") (pinfunction "VIN_3") (pintype "passive"))
      (node (ref "UP01") (pin "4") (pinfunction "EN_4") (pintype "passive"))
    )
    (net (code "80") (name "Net-(UP01-FB)") (class "Default")
      (node (ref "C58") (pin "2") (pinfunction "2_2") (pintype "passive"))
      (node (ref "R53") (pin "1") (pinfunction "1_1") (pintype "passive"))
      (node (ref "R55") (pin "1") (pinfunction "1_1") (pintype "passive"))
      (node (ref "UP01") (pin "9") (pinfunction "FB_9") (pintype "passive"))
    )
    (net (code "81") (name "Net-(UP01-VREF)") (class "Default")
      (node (ref "C57") (pin "1") (pinfunction "1_1") (pintype "passive"))
      (node (ref "R55") (pin "2") (pinfunction "2_2") (pintype "passive"))
      (node (ref "UP01") (pin "10") (pinfunction "VREF_10") (pintype "passive"))
    )
    (net (code "82") (name "VCC_FIBERGYRO_5V") (class "Default")
      (node (ref "C52") (pin "1") (pinfunction "1_1") (pintype "passive"))
      (node (ref "C53") (pin "1") (pinfunction "1_1") (pintype "passive"))
      (node (ref "C54") (pin "2") (pinfunction "2_2") (pintype "passive"))
      (node (ref "R52") (pin "1") (pinfunction "1_1") (pintype "passive"))
      (node (ref "UC01") (pin "6") (pinfunction "OUT_6") (pintype "passive"))
      (node (ref "UP01") (pin "5") (pinfunction "IN_5") (pintype "passive"))
    )
    (net (code "83") (name "VCC_MAGA") (class "Default")
      (node (ref "C69") (pin "1") (pinfunction "1_1") (pintype "passive"))
      (node (ref "C70") (pin "1") (pinfunction "1_1") (pintype "passive"))
      (node (ref "MAGA") (pin "1") (pinfunction "1_1") (pintype "passive"))
      (node (ref "R68") (pin "1") (pinfunction "1_1") (pintype "passive"))
      (node (ref "UC03") (pin "4") (pinfunction "OUT_4") (pintype "passive"))
      (node (ref "UC03") (pin "5") (pinfunction "OUT_5") (pintype "passive"))
      (node (ref "UC03") (pin "6") (pinfunction "OUT_6") (pintype "passive"))
      (node (ref "UC03") (pin "7") (pinfunction "OUT_7") (pintype "passive"))
      (node (ref "UC03") (pin "8") (pinfunction "OUT_8") (pintype "passive"))
    )
    (net (code "84") (name "VCC_MAGB_3.3") (class "Default")
      (node (ref "C84") (pin "1") (pinfunction "1_1") (pintype "passive"))
      (node (ref "C85") (pin "1") (pinfunction "1_1") (pintype "passive"))
      (node (ref "MAGB") (pin "1") (pinfunction "1_1") (pintype "passive"))
      (node (ref "UC05") (pin "6") (pinfunction "OUT_6") (pintype "passive"))
    )
    (net (code "85") (name "VCC_MAGB_5V") (class "Default")
      (node (ref "C80") (pin "1") (pinfunction "1_1") (pintype "passive"))
      (node (ref "C81") (pin "1") (pinfunction "1_1") (pintype "passive"))
      (node (ref "MAGB") (pin "5") (pinfunction "5_5") (pintype "passive"))
      (node (ref "UC04") (pin "6") (pinfunction "OUT_6") (pintype "passive"))
    )
    (net (code "86") (name "VCC_SUNSEN_3.3") (class "Default")
      (node (ref "C91") (pin "1") (pinfunction "1_1") (pintype "passive"))
      (node (ref "C92") (pin "1") (pinfunction "1_1") (pintype "passive"))
      (node (ref "SUNSEN") (pin "1") (pinfunction "1_1") (pintype "passive"))
      (node (ref "UC06") (pin "6") (pinfunction "OUT_6") (pintype "passive"))
    )
    (net (code "87") (name "VOUT_3V3") (class "Default")
      (node (ref "C61") (pin "1") (pinfunction "1_1") (pintype "passive"))
      (node (ref "C62") (pin "1") (pinfunction "1_1") (pintype "passive"))
      (node (ref "C65") (pin "1") (pinfunction "1_1") (pintype "passive"))
      (node (ref "C75") (pin "2") (pinfunction "2_2") (pintype "passive"))
      (node (ref "C76") (pin "1") (pinfunction "1_1") (pintype "passive"))
      (node (ref "C77") (pin "1") (pinfunction "1_1") (pintype "passive"))
      (node (ref "C82") (pin "1") (pinfunction "1_1") (pintype "passive"))
      (node (ref "C83") (pin "1") (pinfunction "1_1") (pintype "passive"))
      (node (ref "C87") (pin "1") (pinfunction "1_1") (pintype "passive"))
      (node (ref "C88") (pin "1") (pinfunction "1_1") (pintype "passive"))
      (node (ref "C89") (pin "1") (pinfunction "1_1") (pintype "passive"))
      (node (ref "C90") (pin "1") (pinfunction "1_1") (pintype "passive"))
      (node (ref "R56") (pin "1") (pinfunction "1_1") (pintype "passive"))
      (node (ref "R58") (pin "1") (pinfunction "1_1") (pintype "passive"))
      (node (ref "R60") (pin "1") (pinfunction "1_1") (pintype "passive"))
      (node (ref "R70") (pin "1") (pinfunction "1_1") (pintype "passive"))
      (node (ref "R71") (pin "1") (pinfunction "1_1") (pintype "passive"))
      (node (ref "R72") (pin "1") (pinfunction "1_1") (pintype "passive"))
      (node (ref "R73") (pin "1") (pinfunction "1_1") (pintype "passive"))
      (node (ref "R76") (pin "1") (pinfunction "1_1") (pintype "passive"))
      (node (ref "R80") (pin "2") (pinfunction "2_2") (pintype "passive"))
      (node (ref "R81") (pin "2") (pinfunction "2_2") (pintype "passive"))
      (node (ref "R82") (pin "2") (pinfunction "2_2") (pintype "passive"))
      (node (ref "R83") (pin "2") (pinfunction "2_2") (pintype "passive"))
      (node (ref "R84") (pin "2") (pinfunction "2_2") (pintype "passive"))
      (node (ref "R85") (pin "2") (pinfunction "2_2") (pintype "passive"))
      (node (ref "R86") (pin "2") (pinfunction "2_2") (pintype "passive"))
      (node (ref "R87") (pin "2") (pinfunction "2_2") (pintype "passive"))
      (node (ref "R88") (pin "1") (pinfunction "1_1") (pintype "passive"))
      (node (ref "R89") (pin "1") (pinfunction "1_1") (pintype "passive"))
      (node (ref "R90") (pin "1") (pinfunction "1_1") (pintype "passive"))
      (node (ref "R91") (pin "1") (pinfunction "1_1") (pintype "passive"))
      (node (ref "R92") (pin "1") (pinfunction "1_1") (pintype "passive"))
      (node (ref "U05") (pin "13") (pinfunction "VCC_13") (pintype "power_in"))
      (node (ref "U05") (pin "14") (pinfunction "VCC_14") (pintype "power_in"))
      (node (ref "U06") (pin "12") (pinfunction "FORCEON_12") (pintype "passive"))
      (node (ref "U06") (pin "15") (pinfunction "VCC_15") (pintype "power_in"))
      (node (ref "U06") (pin "16") (pinfunction "/FORCEOFF_16") (pintype "passive"))
      (node (ref "U07") (pin "1") (pinfunction "VCCA_1") (pintype "power_in"))
      (node (ref "U07") (pin "8") (pinfunction "VCCB_8") (pintype "passive"))
      (node (ref "U08") (pin "1") (pinfunction "VCCA_1") (pintype "power_in"))
      (node (ref "U08") (pin "8") (pinfunction "VCCB_8") (pintype "passive"))
      (node (ref "UC02") (pin "2") (pinfunction "IN_2") (pintype "passive"))
      (node (ref "UC02") (pin "3") (pinfunction "IN_3") (pintype "passive"))
      (node (ref "UC05") (pin "1") (pinfunction "IN_1") (pintype "passive"))
      (node (ref "UC06") (pin "1") (pinfunction "IN_1") (pintype "passive"))
    )
    (net (code "88") (name "VOUT_5V") (class "Default")
      (node (ref "C101") (pin "1") (pinfunction "1_1") (pintype "passive"))
      (node (ref "C102") (pin "1") (pinfunction "1_1") (pintype "passive"))
      (node (ref "C105") (pin "1") (pinfunction "1_1") (pintype "passive"))
      (node (ref "C106") (pin "1") (pinfunction "1_1") (pintype "passive"))
      (node (ref "C50") (pin "1") (pinfunction "1_1") (pintype "passive"))
      (node (ref "C51") (pin "1") (pinfunction "1_1") (pintype "passive"))
      (node (ref "C78") (pin "1") (pinfunction "1_1") (pintype "passive"))
      (node (ref "C79") (pin "1") (pinfunction "1_1") (pintype "passive"))
      (node (ref "C93") (pin "1") (pinfunction "1_1") (pintype "passive"))
      (node (ref "C94") (pin "1") (pinfunction "1_1") (pintype "passive"))
      (node (ref "C97") (pin "1") (pinfunction "1_1") (pintype "passive"))
      (node (ref "C98") (pin "1") (pinfunction "1_1") (pintype "passive"))
      (node (ref "R100") (pin "1") (pinfunction "1_1") (pintype "passive"))
      (node (ref "R50") (pin "1") (pinfunction "1_1") (pintype "passive"))
      (node (ref "R74") (pin "1") (pinfunction "1_1") (pintype "passive"))
      (node (ref "R94") (pin "1") (pinfunction "1_1") (pintype "passive"))
      (node (ref "R96") (pin "1") (pinfunction "1_1") (pintype "passive"))
      (node (ref "R98") (pin "1") (pinfunction "1_1") (pintype "passive"))
      (node (ref "UC01") (pin "1") (pinfunction "IN_1") (pintype "passive"))
      (node (ref "UC04") (pin "1") (pinfunction "IN_1") (pintype "passive"))
      (node (ref "UC07") (pin "2") (pinfunction "IN_2") (pintype "passive"))
      (node (ref "UC07") (pin "3") (pinfunction "IN_3") (pintype "passive"))
      (node (ref "UC08") (pin "2") (pinfunction "IN_2") (pintype "passive"))
      (node (ref "UC08") (pin "3") (pinfunction "IN_3") (pintype "passive"))
      (node (ref "UC09") (pin "2") (pinfunction "IN_2") (pintype "passive"))
      (node (ref "UC09") (pin "3") (pinfunction "IN_3") (pintype "passive"))
      (node (ref "UC10") (pin "2") (pinfunction "IN_2") (pintype "passive"))
      (node (ref "UC10") (pin "3") (pinfunction "IN_3") (pintype "passive"))
    )
    (net (code "89") (name "VOUT_BATT") (class "Default")
      (node (ref "C66") (pin "1") (pinfunction "1_1") (pintype "passive"))
      (node (ref "C67") (pin "1") (pinfunction "1_1") (pintype "passive"))
      (node (ref "UC03") (pin "10") (pinfunction "IN_10") (pintype "passive"))
      (node (ref "UC03") (pin "11") (pinfunction "IN_11") (pintype "passive"))
      (node (ref "UC03") (pin "12") (pinfunction "IN_12") (pintype "passive"))
      (node (ref "UC03") (pin "13") (pinfunction "IN_13") (pintype "passive"))
      (node (ref "UC03") (pin "9") (pinfunction "IN_9") (pintype "passive"))
    )
    (net (code "90") (name "V_Ant1_5V") (class "Default")
      (node (ref "C103") (pin "1") (pinfunction "1_1") (pintype "passive"))
      (node (ref "C104") (pin "1") (pinfunction "1_1") (pintype "passive"))
      (node (ref "PAV1") (pin "2") (pinfunction "2_2") (pintype "passive"))
      (node (ref "UC09") (pin "6") (pinfunction "OUT_6") (pintype "passive"))
      (node (ref "UC09") (pin "7") (pinfunction "OUT_7") (pintype "passive"))
    )
    (net (code "91") (name "V_Ant2_5V") (class "Default")
      (node (ref "C107") (pin "1") (pinfunction "1_1") (pintype "passive"))
      (node (ref "C108") (pin "1") (pinfunction "1_1") (pintype "passive"))
      (node (ref "PAV2") (pin "2") (pinfunction "2_2") (pintype "passive"))
      (node (ref "UC10") (pin "6") (pinfunction "OUT_6") (pintype "passive"))
      (node (ref "UC10") (pin "7") (pinfunction "OUT_7") (pintype "passive"))
    )
    (net (code "92") (name "V_FIBERGYRO+3.3") (class "Default")
      (node (ref "C63") (pin "1") (pinfunction "1_1") (pintype "passive"))
      (node (ref "C64") (pin "1") (pinfunction "1_1") (pintype "passive"))
      (node (ref "FIBER") (pin "3") (pinfunction "3_3") (pintype "passive"))
      (node (ref "UC02") (pin "6") (pinfunction "OUT_6") (pintype "passive"))
      (node (ref "UC02") (pin "7") (pinfunction "OUT_7") (pintype "passive"))
    )
    (net (code "93") (name "V_FIBERGYRO-3.3") (class "Default")
      (node (ref "C59") (pin "2") (pinfunction "2_2") (pintype "passive"))
      (node (ref "C60") (pin "2") (pinfunction "2_2") (pintype "passive"))
      (node (ref "D1") (pin "1") (pinfunction "A_1") (pintype "passive"))
      (node (ref "FIBER") (pin "5") (pinfunction "5_5") (pintype "passive"))
      (node (ref "R53") (pin "2") (pinfunction "2_2") (pintype "passive"))
      (node (ref "R54") (pin "2") (pinfunction "2_2") (pintype "passive"))
      (node (ref "UP01") (pin "8") (pinfunction "OUT_8") (pintype "passive"))
    )
    (net (code "94") (name "V_Sb1_5V") (class "Default")
      (node (ref "C95") (pin "1") (pinfunction "1_1") (pintype "passive"))
      (node (ref "C96") (pin "1") (pinfunction "1_1") (pintype "passive"))
      (node (ref "SBV1") (pin "2") (pinfunction "2_2") (pintype "passive"))
      (node (ref "UC07") (pin "6") (pinfunction "OUT_6") (pintype "passive"))
      (node (ref "UC07") (pin "7") (pinfunction "OUT_7") (pintype "passive"))
    )
    (net (code "95") (name "V_Sb2_5V") (class "Default")
      (node (ref "C100") (pin "1") (pinfunction "1_1") (pintype "passive"))
      (node (ref "C99") (pin "1") (pinfunction "1_1") (pintype "passive"))
      (node (ref "SBV2") (pin "2") (pinfunction "2_2") (pintype "passive"))
      (node (ref "UC08") (pin "6") (pinfunction "OUT_6") (pintype "passive"))
      (node (ref "UC08") (pin "7") (pinfunction "OUT_7") (pintype "passive"))
    )
    (net (code "96") (name "unconnected-(U05-NC-Pad1)") (class "Default")
      (node (ref "U05") (pin "1") (pinfunction "NC_1") (pintype "passive"))
    )
    (net (code "97") (name "unconnected-(U05-NC-Pad8)") (class "Default")
      (node (ref "U05") (pin "8") (pinfunction "NC_8") (pintype "power_in"))
    )
  )
)
